# PIC16F628A-I.net
KiCad netlist of a schematic drawn in EAGLE
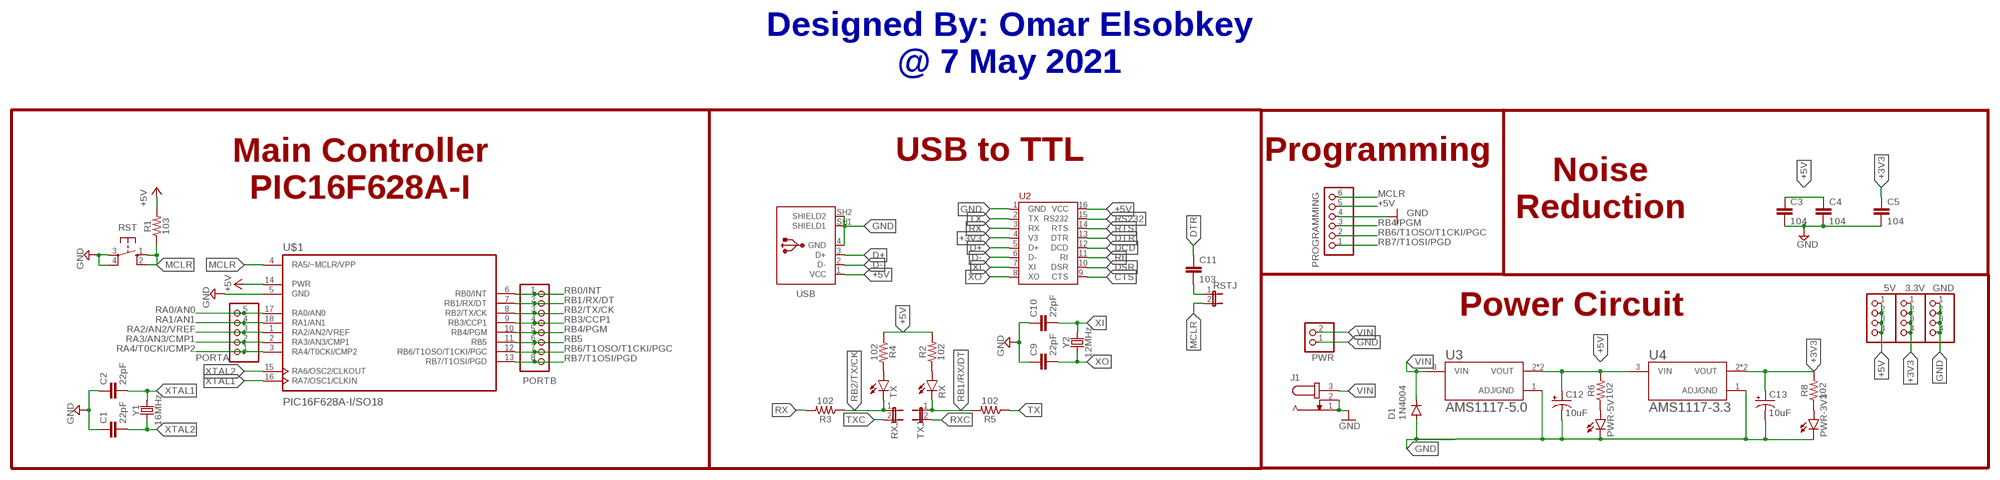
[diagram p0: schematic, sheet 1]

(export (version "E")
  (design (tool "Eeschema 10.0.6"))
  (components
    (comp (ref "3.3V")
      (value "PINHD-1X4")
      (footprint "eagle-import:1X04")
      (libsource (lib "eagle-import") (part "PINHD-1X4"))
    )
    (comp (ref "5V")
      (value "PINHD-1X4")
      (footprint "eagle-import:1X04")
      (libsource (lib "eagle-import") (part "PINHD-1X4"))
    )
    (comp (ref "C1")
      (value "22pF")
      (footprint "eagle-import:CAP-PTH-2.54")
      (libsource (lib "eagle-import") (part "22PF-PTH-2.54MM-200V-5%"))
    )
    (comp (ref "C2")
      (value "22pF")
      (footprint "eagle-import:CAP-PTH-2.54")
      (libsource (lib "eagle-import") (part "22PF-PTH-2.54MM-200V-5%"))
    )
    (comp (ref "C3")
      (value "104")
      (footprint "eagle-import:CAP-PTH-2.54")
      (libsource (lib "eagle-import") (part "22PF-PTH-2.54MM-200V-5%"))
    )
    (comp (ref "C4")
      (value "104")
      (footprint "eagle-import:CAP-PTH-2.54")
      (libsource (lib "eagle-import") (part "22PF-PTH-2.54MM-200V-5%"))
    )
    (comp (ref "C5")
      (value "104")
      (footprint "eagle-import:CAP-PTH-2.54")
      (libsource (lib "eagle-import") (part "22PF-PTH-2.54MM-200V-5%"))
    )
    (comp (ref "C9")
      (value "22pF")
      (footprint "eagle-import:CAP-PTH-2.54")
      (libsource (lib "eagle-import") (part "22PF-PTH-2.54MM-200V-5%"))
    )
    (comp (ref "C10")
      (value "22pF")
      (footprint "eagle-import:CAP-PTH-2.54")
      (libsource (lib "eagle-import") (part "22PF-PTH-2.54MM-200V-5%"))
    )
    (comp (ref "C11")
      (value "103")
      (footprint "eagle-import:CAP-PTH-2.54")
      (libsource (lib "eagle-import") (part "22PF-PTH-2.54MM-200V-5%"))
    )
    (comp (ref "C12")
      (value "10uF")
      (footprint "eagle-import:CPOL-RADIAL-2.5MM-5MM-KIT")
      (libsource (lib "eagle-import") (part "10UF-POLAR-RADIAL-2.5MM-KIT-25V-20%"))
    )
    (comp (ref "C13")
      (value "10uF")
      (footprint "eagle-import:CPOL-RADIAL-2.5MM-5MM-KIT")
      (libsource (lib "eagle-import") (part "10UF-POLAR-RADIAL-2.5MM-KIT-25V-20%"))
    )
    (comp (ref "D1")
      (value "1N4004")
      (footprint "eagle-import:DO41-10")
      (libsource (lib "eagle-import") (part "1N4004"))
    )
    (comp (ref "GND")
      (value "PINHD-1X4")
      (footprint "eagle-import:1X04")
      (libsource (lib "eagle-import") (part "PINHD-1X4"))
    )
    (comp (ref "J1")
      (value "JACK-PLUG0")
      (footprint "eagle-import:SPC4077")
      (libsource (lib "eagle-import") (part "JACK-PLUG0"))
    )
    (comp (ref "PORTA")
      (value "PINHD-1X5")
      (footprint "eagle-import:1X05")
      (libsource (lib "eagle-import") (part "PINHD-1X5"))
    )
    (comp (ref "PORTB")
      (value "PINHD-1X8")
      (footprint "eagle-import:1X08")
      (libsource (lib "eagle-import") (part "PINHD-1X8"))
    )
    (comp (ref "PROGRAMMING")
      (value "PINHD-1X6")
      (footprint "eagle-import:1X06")
      (libsource (lib "eagle-import") (part "PINHD-1X6"))
    )
    (comp (ref "PWR")
      (value "PINHD-1X2")
      (footprint "eagle-import:1X02")
      (libsource (lib "eagle-import") (part "PINHD-1X2"))
    )
    (comp (ref "PWR-3V3")
      (value "LEDCHIP-LED0805")
      (footprint "eagle-import:CHIP-LED0805")
      (libsource (lib "eagle-import") (part "LEDCHIP-LED0805"))
    )
    (comp (ref "PWR-5V")
      (value "LEDCHIP-LED0805")
      (footprint "eagle-import:CHIP-LED0805")
      (libsource (lib "eagle-import") (part "LEDCHIP-LED0805"))
    )
    (comp (ref "R1")
      (value "103")
      (footprint "eagle-import:1206")
      (libsource (lib "eagle-import") (part "RESISTOR1206"))
    )
    (comp (ref "R2")
      (value "102")
      (footprint "eagle-import:1206")
      (libsource (lib "eagle-import") (part "RESISTOR1206"))
    )
    (comp (ref "R3")
      (value "102")
      (footprint "eagle-import:1206")
      (libsource (lib "eagle-import") (part "RESISTOR1206"))
    )
    (comp (ref "R4")
      (value "102")
      (footprint "eagle-import:1206")
      (libsource (lib "eagle-import") (part "RESISTOR1206"))
    )
    (comp (ref "R5")
      (value "102")
      (footprint "eagle-import:1206")
      (libsource (lib "eagle-import") (part "RESISTOR1206"))
    )
    (comp (ref "R6")
      (value "102")
      (footprint "eagle-import:1206")
      (libsource (lib "eagle-import") (part "RESISTOR1206"))
    )
    (comp (ref "R8")
      (value "102")
      (footprint "eagle-import:1206")
      (libsource (lib "eagle-import") (part "RESISTOR1206"))
    )
    (comp (ref "RST")
      (value "10-XX")
      (footprint "eagle-import:B3F-10XX")
      (fields (field (name "MPN") "B3F-1000"))
      (libsource (lib "eagle-import") (part "10-XX"))
    )
    (comp (ref "RSTJ")
      (value "JP1E")
      (footprint "eagle-import:JP1")
      (libsource (lib "eagle-import") (part "JP1E"))
    )
    (comp (ref "RX")
      (value "LEDCHIP-LED0805")
      (footprint "eagle-import:CHIP-LED0805")
      (libsource (lib "eagle-import") (part "LEDCHIP-LED0805"))
    )
    (comp (ref "RXJ")
      (value "JP1E")
      (footprint "eagle-import:JP1")
      (libsource (lib "eagle-import") (part "JP1E"))
    )
    (comp (ref "TX")
      (value "LEDCHIP-LED0805")
      (footprint "eagle-import:CHIP-LED0805")
      (libsource (lib "eagle-import") (part "LEDCHIP-LED0805"))
    )
    (comp (ref "TXJ")
      (value "JP1E")
      (footprint "eagle-import:JP1")
      (libsource (lib "eagle-import") (part "JP1E"))
    )
    (comp (ref "U$1")
      (value "PIC16F628A-I/SO18")
      (footprint "eagle-import:SOIC127P1030X265-18N")
      (fields (field (name "MF") "Microchip Technology") (field (name "MP") "PIC16F628A-I/SO"))
      (libsource (lib "eagle-import") (part "PIC16F628A-I/SO18"))
    )
    (comp (ref "U2")
      (value "CH340G")
      (footprint "eagle-import:SOP-16")
      (libsource (lib "eagle-import") (part "CH340G"))
    )
    (comp (ref "U3")
      (value "AMS1117-5.0")
      (footprint "eagle-import:AMS1117-5.0")
      (fields (field (name "MF") "Advanced Monolithic Systems"))
      (libsource (lib "eagle-import") (part "AMS1117-5.0"))
    )
    (comp (ref "U4")
      (value "AMS1117-3.3")
      (footprint "eagle-import:AMS1117-5.0")
      (fields (field (name "MF") "Advanced Monolithic Systems") (field (name "MP") "AMS1117-5.0"))
      (libsource (lib "eagle-import") (part "AMS1117-5.0"))
    )
    (comp (ref "USB")
      (value "61729-1011")
      (footprint "eagle-import:61729-1011BLF")
      (fields (field (name "MANUFACTURER") "Amphenol ICC (FCI)") (field (name "MPN") "61729-1011BLF"))
      (libsource (lib "eagle-import") (part "61729-1011"))
    )
    (comp (ref "Y1")
      (value "16MHz")
      (footprint "eagle-import:HC49U")
      (libsource (lib "eagle-import") (part "CRYSTALPTH-HC49UV"))
    )
    (comp (ref "Y2")
      (value "12MHz")
      (footprint "eagle-import:HC49U")
      (libsource (lib "eagle-import") (part "CRYSTALPTH-HC49UV"))
    )
  )
  (nets
    (net (code "1") (name "+3V3") (class "Default")
      (node (ref "3.3V") (pin "1") (pinfunction "1_1") (pintype "passive"))
      (node (ref "3.3V") (pin "2") (pinfunction "2_2") (pintype "passive"))
      (node (ref "3.3V") (pin "3") (pinfunction "3_3") (pintype "passive"))
      (node (ref "3.3V") (pin "4") (pinfunction "4_4") (pintype "passive"))
      (node (ref "C13") (pin "1") (pinfunction "+_1") (pintype "passive"))
      (node (ref "C5") (pin "1") (pinfunction "1_1") (pintype "passive"))
      (node (ref "R8") (pin "2") (pinfunction "2_2") (pintype "passive"))
      (node (ref "U2") (pin "4") (pinfunction "V3_4") (pintype "bidirectional"))
      (node (ref "U4") (pin "2") (pinfunction "VOUT_2") (pintype "output"))
      (node (ref "U4") (pin "4") (pinfunction "VOUT_4") (pintype "output"))
    )
    (net (code "2") (name "+5V") (class "Default")
      (node (ref "5V") (pin "1") (pinfunction "1_1") (pintype "passive"))
      (node (ref "5V") (pin "2") (pinfunction "2_2") (pintype "passive"))
      (node (ref "5V") (pin "3") (pinfunction "3_3") (pintype "passive"))
      (node (ref "5V") (pin "4") (pinfunction "4_4") (pintype "passive"))
      (node (ref "C12") (pin "1") (pinfunction "+_1") (pintype "passive"))
      (node (ref "C3") (pin "1") (pinfunction "1_1") (pintype "passive"))
      (node (ref "C4") (pin "1") (pinfunction "1_1") (pintype "passive"))
      (node (ref "PROGRAMMING") (pin "5") (pinfunction "5_5") (pintype "passive"))
      (node (ref "R1") (pin "2") (pinfunction "2_2") (pintype "passive"))
      (node (ref "R2") (pin "2") (pinfunction "2_2") (pintype "passive"))
      (node (ref "R4") (pin "1") (pinfunction "1_1") (pintype "passive"))
      (node (ref "R6") (pin "2") (pinfunction "2_2") (pintype "passive"))
      (node (ref "U$1") (pin "14") (pinfunction "PWR_14") (pintype "power_in"))
      (node (ref "U2") (pin "16") (pinfunction "VCC_16") (pintype "bidirectional"))
      (node (ref "U3") (pin "2") (pinfunction "VOUT_2") (pintype "output"))
      (node (ref "U3") (pin "4") (pinfunction "VOUT_4") (pintype "output"))
      (node (ref "U4") (pin "3") (pinfunction "VIN_3") (pintype "input"))
      (node (ref "USB") (pin "1") (pinfunction "VCC_1") (pintype "power_in"))
    )
    (net (code "3") (name "/RA0{slash}AN0") (class "Default")
      (node (ref "PORTA") (pin "5") (pinfunction "5_5") (pintype "passive"))
      (node (ref "U$1") (pin "17") (pinfunction "RA0/AN0_17") (pintype "bidirectional"))
    )
    (net (code "4") (name "/RA1{slash}AN1") (class "Default")
      (node (ref "PORTA") (pin "4") (pinfunction "4_4") (pintype "passive"))
      (node (ref "U$1") (pin "18") (pinfunction "RA1/AN1_18") (pintype "bidirectional"))
    )
    (net (code "5") (name "/RA2{slash}AN2{slash}VREF") (class "Default")
      (node (ref "PORTA") (pin "3") (pinfunction "3_3") (pintype "passive"))
      (node (ref "U$1") (pin "1") (pinfunction "RA2/AN2/VREF_1") (pintype "bidirectional"))
    )
    (net (code "6") (name "/RA3{slash}AN3{slash}CMP1") (class "Default")
      (node (ref "PORTA") (pin "2") (pinfunction "2_2") (pintype "passive"))
      (node (ref "U$1") (pin "2") (pinfunction "RA3/AN3/CMP1_2") (pintype "bidirectional"))
    )
    (net (code "7") (name "/RA4{slash}T0CKI{slash}CMP2") (class "Default")
      (node (ref "PORTA") (pin "1") (pinfunction "1_1") (pintype "passive"))
      (node (ref "U$1") (pin "3") (pinfunction "RA4/T0CKI/CMP2_3") (pintype "bidirectional"))
    )
    (net (code "8") (name "/RB0{slash}INT") (class "Default")
      (node (ref "PORTB") (pin "1") (pinfunction "1_1") (pintype "passive"))
      (node (ref "U$1") (pin "6") (pinfunction "RB0/INT_6") (pintype "input"))
    )
    (net (code "9") (name "/RB3{slash}CCP1") (class "Default")
      (node (ref "PORTB") (pin "4") (pinfunction "4_4") (pintype "passive"))
      (node (ref "U$1") (pin "9") (pinfunction "RB3/CCP1_9") (pintype "bidirectional"))
    )
    (net (code "10") (name "/RB4{slash}PGM") (class "Default")
      (node (ref "PORTB") (pin "5") (pinfunction "5_5") (pintype "passive"))
      (node (ref "PROGRAMMING") (pin "3") (pinfunction "3_3") (pintype "passive"))
      (node (ref "U$1") (pin "10") (pinfunction "RB4/PGM_10") (pintype "bidirectional"))
    )
    (net (code "11") (name "/RB5") (class "Default")
      (node (ref "PORTB") (pin "6") (pinfunction "6_6") (pintype "passive"))
      (node (ref "U$1") (pin "11") (pinfunction "RB5_11") (pintype "bidirectional"))
    )
    (net (code "12") (name "/RB6{slash}T1OSO{slash}T1CKI{slash}PGC") (class "Default")
      (node (ref "PORTB") (pin "7") (pinfunction "7_7") (pintype "passive"))
      (node (ref "PROGRAMMING") (pin "2") (pinfunction "2_2") (pintype "passive"))
      (node (ref "U$1") (pin "12") (pinfunction "RB6/T1OSO/T1CKI/PGC_12") (pintype "bidirectional"))
    )
    (net (code "13") (name "/RB7{slash}T1OSI{slash}PGD") (class "Default")
      (node (ref "PORTB") (pin "8") (pinfunction "8_8") (pintype "passive"))
      (node (ref "PROGRAMMING") (pin "1") (pinfunction "1_1") (pintype "passive"))
      (node (ref "U$1") (pin "13") (pinfunction "RB7/T1OSI/PGD_13") (pintype "bidirectional"))
    )
    (net (code "14") (name "CTS") (class "Default")
      (node (ref "U2") (pin "9") (pinfunction "CTS_9") (pintype "bidirectional"))
    )
    (net (code "15") (name "D+") (class "Default")
      (node (ref "U2") (pin "5") (pinfunction "D+_5") (pintype "bidirectional"))
      (node (ref "USB") (pin "3") (pinfunction "D+_3") (pintype "bidirectional"))
    )
    (net (code "16") (name "D-") (class "Default")
      (node (ref "U2") (pin "6") (pinfunction "D-_6") (pintype "bidirectional"))
      (node (ref "USB") (pin "2") (pinfunction "D-_2") (pintype "bidirectional"))
    )
    (net (code "17") (name "DCD") (class "Default")
      (node (ref "U2") (pin "12") (pinfunction "DCD_12") (pintype "bidirectional"))
    )
    (net (code "18") (name "DSR") (class "Default")
      (node (ref "U2") (pin "10") (pinfunction "DSR_10") (pintype "bidirectional"))
    )
    (net (code "19") (name "DTR") (class "Default")
      (node (ref "C11") (pin "1") (pinfunction "1_1") (pintype "passive"))
      (node (ref "U2") (pin "13") (pinfunction "DTR_13") (pintype "bidirectional"))
    )
    (net (code "20") (name "GND") (class "Default")
      (node (ref "C1") (pin "1") (pinfunction "1_1") (pintype "passive"))
      (node (ref "C10") (pin "1") (pinfunction "1_1") (pintype "passive"))
      (node (ref "C12") (pin "2") (pinfunction "-_2") (pintype "passive"))
      (node (ref "C13") (pin "2") (pinfunction "-_2") (pintype "passive"))
      (node (ref "C2") (pin "1") (pinfunction "1_1") (pintype "passive"))
      (node (ref "C3") (pin "2") (pinfunction "2_2") (pintype "passive"))
      (node (ref "C4") (pin "2") (pinfunction "2_2") (pintype "passive"))
      (node (ref "C5") (pin "2") (pinfunction "2_2") (pintype "passive"))
      (node (ref "C9") (pin "1") (pinfunction "1_1") (pintype "passive"))
      (node (ref "D1") (pin "A") (pinfunction "A_A") (pintype "passive"))
      (node (ref "GND") (pin "1") (pinfunction "1_1") (pintype "passive"))
      (node (ref "GND") (pin "2") (pinfunction "2_2") (pintype "passive"))
      (node (ref "GND") (pin "3") (pinfunction "3_3") (pintype "passive"))
      (node (ref "GND") (pin "4") (pinfunction "4_4") (pintype "passive"))
      (node (ref "J1") (pin "1") (pinfunction "1_1") (pintype "passive"))
      (node (ref "J1") (pin "2") (pinfunction "2_2") (pintype "passive"))
      (node (ref "PROGRAMMING") (pin "4") (pinfunction "4_4") (pintype "passive"))
      (node (ref "PWR") (pin "1") (pinfunction "1_1") (pintype "passive"))
      (node (ref "PWR-3V3") (pin "C") (pinfunction "C_C") (pintype "passive"))
      (node (ref "PWR-5V") (pin "C") (pinfunction "C_C") (pintype "passive"))
      (node (ref "RST") (pin "3") (pinfunction "P_3") (pintype "passive"))
      (node (ref "RST") (pin "4") (pinfunction "P1_4") (pintype "passive"))
      (node (ref "U$1") (pin "5") (pinfunction "GND_5") (pintype "power_in"))
      (node (ref "U2") (pin "1") (pinfunction "GND_1") (pintype "bidirectional"))
      (node (ref "U3") (pin "1") (pinfunction "ADJ/GND_1") (pintype "power_in"))
      (node (ref "U4") (pin "1") (pinfunction "ADJ/GND_1") (pintype "power_in"))
      (node (ref "USB") (pin "4") (pinfunction "GND_4") (pintype "power_in"))
      (node (ref "USB") (pin "SH1") (pinfunction "SHIELD1_SH1") (pintype "power_in"))
      (node (ref "USB") (pin "SH2") (pinfunction "SHIELD2_SH2") (pintype "power_in"))
    )
    (net (code "21") (name "MCLR") (class "Default")
      (node (ref "PROGRAMMING") (pin "6") (pinfunction "6_6") (pintype "passive"))
      (node (ref "R1") (pin "1") (pinfunction "1_1") (pintype "passive"))
      (node (ref "RST") (pin "1") (pinfunction "S_1") (pintype "passive"))
      (node (ref "RST") (pin "2") (pinfunction "S1_2") (pintype "passive"))
      (node (ref "RSTJ") (pin "2") (pinfunction "2_2") (pintype "passive"))
      (node (ref "U$1") (pin "4") (pinfunction "RA5/~{MCLR/VPP}_4") (pintype "bidirectional"))
    )
    (net (code "22") (name "Net-(C11-Pad2)") (class "Default")
      (node (ref "C11") (pin "2") (pinfunction "2_2") (pintype "passive"))
      (node (ref "RSTJ") (pin "1") (pinfunction "1_1") (pintype "passive"))
    )
    (net (code "23") (name "Net-(PWR-3V3-PadA)") (class "Default")
      (node (ref "PWR-3V3") (pin "A") (pinfunction "A_A") (pintype "passive"))
      (node (ref "R8") (pin "1") (pinfunction "1_1") (pintype "passive"))
    )
    (net (code "24") (name "Net-(PWR-5V-PadA)") (class "Default")
      (node (ref "PWR-5V") (pin "A") (pinfunction "A_A") (pintype "passive"))
      (node (ref "R6") (pin "1") (pinfunction "1_1") (pintype "passive"))
    )
    (net (code "25") (name "Net-(R2-Pad1)") (class "Default")
      (node (ref "R2") (pin "1") (pinfunction "1_1") (pintype "passive"))
      (node (ref "RX") (pin "A") (pinfunction "A_A") (pintype "passive"))
    )
    (net (code "26") (name "Net-(R4-Pad2)") (class "Default")
      (node (ref "R4") (pin "2") (pinfunction "2_2") (pintype "passive"))
      (node (ref "TX") (pin "A") (pinfunction "A_A") (pintype "passive"))
    )
    (net (code "27") (name "RB1{slash}RX{slash}DT") (class "Default")
      (node (ref "PORTB") (pin "2") (pinfunction "2_2") (pintype "passive"))
      (node (ref "R5") (pin "2") (pinfunction "2_2") (pintype "passive"))
      (node (ref "RX") (pin "C") (pinfunction "C_C") (pintype "passive"))
      (node (ref "TXJ") (pin "1") (pinfunction "1_1") (pintype "passive"))
      (node (ref "U$1") (pin "7") (pinfunction "RB1/RX/DT_7") (pintype "bidirectional"))
    )
    (net (code "28") (name "RB2{slash}TX{slash}CK") (class "Default")
      (node (ref "PORTB") (pin "3") (pinfunction "3_3") (pintype "passive"))
      (node (ref "R3") (pin "1") (pinfunction "1_1") (pintype "passive"))
      (node (ref "RXJ") (pin "1") (pinfunction "1_1") (pintype "passive"))
      (node (ref "TX") (pin "C") (pinfunction "C_C") (pintype "passive"))
      (node (ref "U$1") (pin "8") (pinfunction "RB2/TX/CK_8") (pintype "bidirectional"))
    )
    (net (code "29") (name "RI") (class "Default")
      (node (ref "U2") (pin "11") (pinfunction "RI_11") (pintype "bidirectional"))
    )
    (net (code "30") (name "RS232") (class "Default")
      (node (ref "U2") (pin "15") (pinfunction "RS232_15") (pintype "bidirectional"))
    )
    (net (code "31") (name "RTS") (class "Default")
      (node (ref "U2") (pin "14") (pinfunction "RTS_14") (pintype "bidirectional"))
    )
    (net (code "32") (name "RX") (class "Default")
      (node (ref "R3") (pin "2") (pinfunction "2_2") (pintype "passive"))
      (node (ref "U2") (pin "3") (pinfunction "RX_3") (pintype "bidirectional"))
    )
    (net (code "33") (name "RXC") (class "Default")
      (node (ref "TXJ") (pin "2") (pinfunction "2_2") (pintype "passive"))
    )
    (net (code "34") (name "TX") (class "Default")
      (node (ref "R5") (pin "1") (pinfunction "1_1") (pintype "passive"))
      (node (ref "U2") (pin "2") (pinfunction "TX_2") (pintype "bidirectional"))
    )
    (net (code "35") (name "TXC") (class "Default")
      (node (ref "RXJ") (pin "2") (pinfunction "2_2") (pintype "passive"))
    )
    (net (code "36") (name "VIN") (class "Default")
      (node (ref "D1") (pin "C") (pinfunction "C_C") (pintype "passive"))
      (node (ref "J1") (pin "3") (pinfunction "3_3") (pintype "passive"))
      (node (ref "PWR") (pin "2") (pinfunction "2_2") (pintype "passive"))
      (node (ref "U3") (pin "3") (pinfunction "VIN_3") (pintype "input"))
    )
    (net (code "37") (name "XI") (class "Default")
      (node (ref "C10") (pin "2") (pinfunction "2_2") (pintype "passive"))
      (node (ref "U2") (pin "7") (pinfunction "XI_7") (pintype "bidirectional"))
      (node (ref "Y2") (pin "2") (pinfunction "2_2") (pintype "passive"))
    )
    (net (code "38") (name "XO") (class "Default")
      (node (ref "C9") (pin "2") (pinfunction "2_2") (pintype "passive"))
      (node (ref "U2") (pin "8") (pinfunction "XO_8") (pintype "bidirectional"))
      (node (ref "Y2") (pin "1") (pinfunction "1_1") (pintype "passive"))
    )
    (net (code "39") (name "XTAL1") (class "Default")
      (node (ref "C2") (pin "2") (pinfunction "2_2") (pintype "passive"))
      (node (ref "U$1") (pin "16") (pinfunction "RA7/OSC1/CLKIN_16") (pintype "input"))
      (node (ref "Y1") (pin "2") (pinfunction "2_2") (pintype "passive"))
    )
    (net (code "40") (name "XTAL2") (class "Default")
      (node (ref "C1") (pin "2") (pinfunction "2_2") (pintype "passive"))
      (node (ref "U$1") (pin "15") (pinfunction "RA6/OSC2/CLKOUT_15") (pintype "bidirectional"))
      (node (ref "Y1") (pin "1") (pinfunction "1_1") (pintype "passive"))
    )
  )
)
